# MotorsAndLighthouseShield.net
KiCad netlist of a schematic drawn in EAGLE
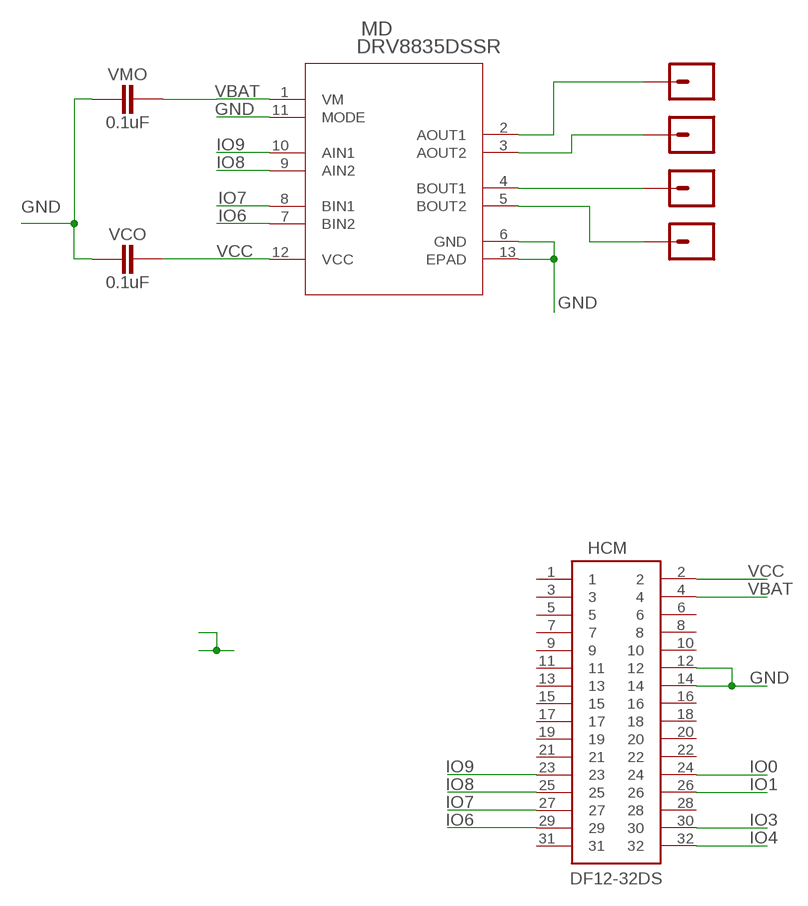
[diagram p0: schematic, sheet 1]
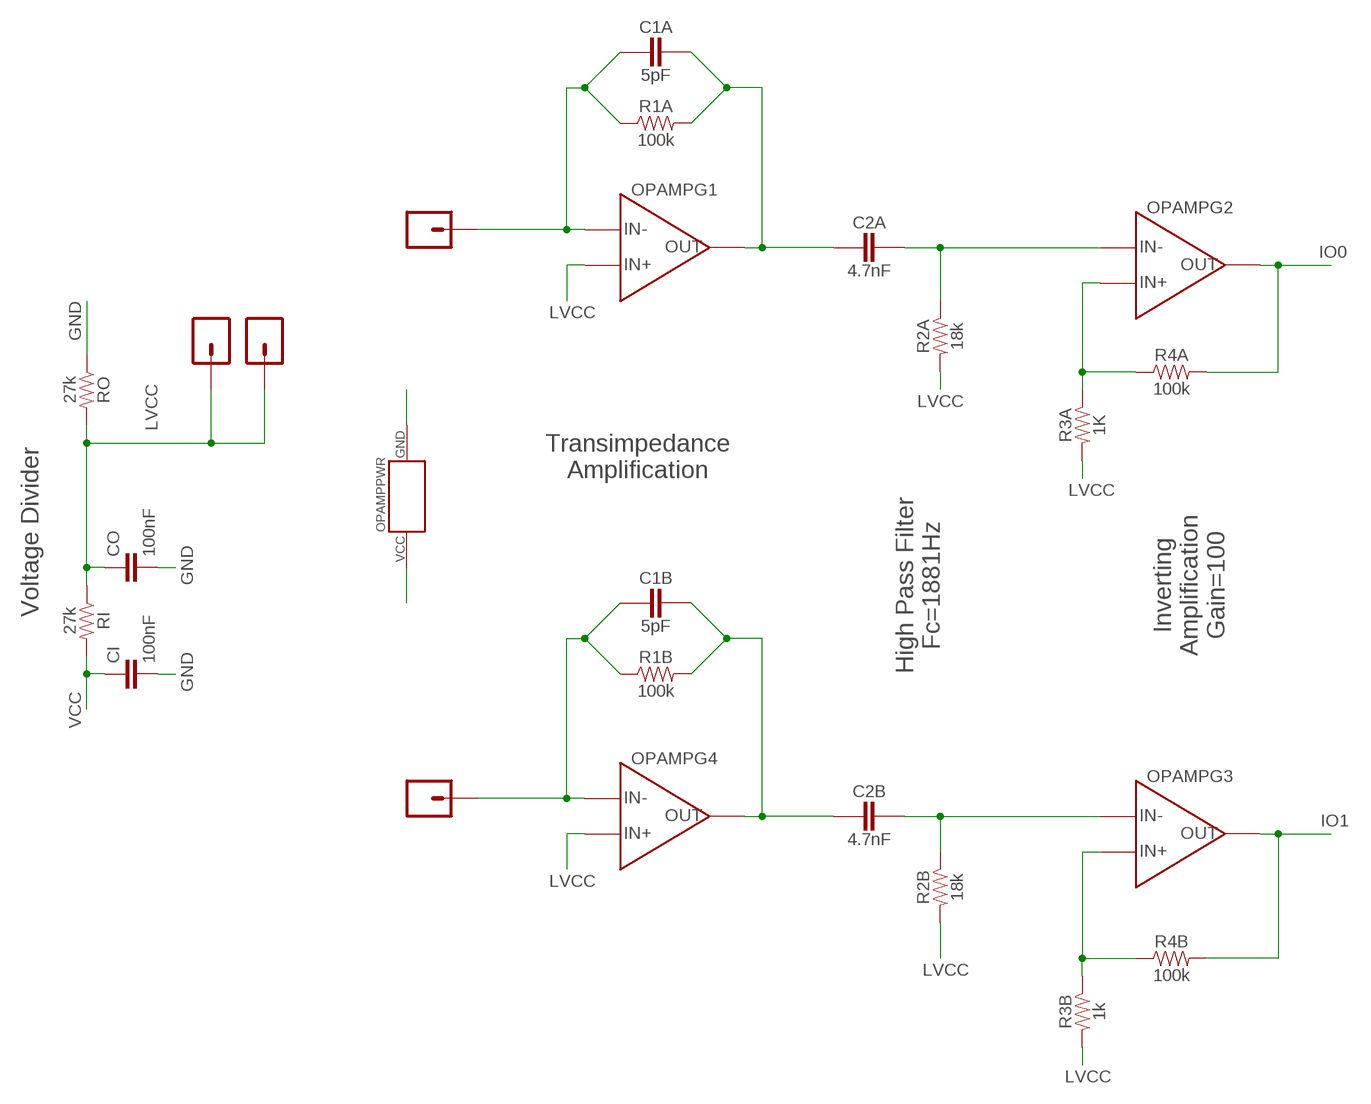
[diagram p1: schematic, sheet 2]

(export (version "E")
  (design (tool "Eeschema 10.0.6"))
  (components
    (comp (ref "AO1")
      (value "SINGLE-THROUGH-HOLE")
      (footprint "eagle-import:SINGLE-THROUGH-HOLE")
      (libsource (lib "eagle-import") (part "SINGLE-THROUGH-HOLE"))
    )
    (comp (ref "AO2")
      (value "SINGLE-THROUGH-HOLE")
      (footprint "eagle-import:SINGLE-THROUGH-HOLE")
      (libsource (lib "eagle-import") (part "SINGLE-THROUGH-HOLE"))
    )
    (comp (ref "B02")
      (value "SINGLE-THROUGH-HOLE")
      (footprint "eagle-import:SINGLE-THROUGH-HOLE")
      (libsource (lib "eagle-import") (part "SINGLE-THROUGH-HOLE"))
    )
    (comp (ref "BO1")
      (value "SINGLE-THROUGH-HOLE")
      (footprint "eagle-import:SINGLE-THROUGH-HOLE")
      (libsource (lib "eagle-import") (part "SINGLE-THROUGH-HOLE"))
    )
    (comp (ref "HCM")
      (value "HIROSE-DF12-32DSMALE")
      (footprint "eagle-import:DF12(3.0)-32DS-0.5V(86)-MALE")
      (libsource (lib "eagle-import") (part "HIROSE-DF12-32DSMALE"))
    )
    (comp (ref "MD")
      (value "DRV8835DSSR")
      (footprint "eagle-import:DSS12_P9X2")
      (libsource (lib "eagle-import") (part "DRV8835DSSR"))
    )
    (comp (ref "VCO")
      (value "0.1uF")
      (footprint "eagle-import:PASSIVE-0603")
      (libsource (lib "eagle-import") (part "CAPACITOR"))
    )
    (comp (ref "VMO")
      (value "0.1uF")
      (footprint "eagle-import:PASSIVE-0603")
      (libsource (lib "eagle-import") (part "CAPACITOR"))
    )
    (comp (ref "C1A")
      (value "5pF")
      (footprint "eagle-import:PASSIVE-0603")
      (libsource (lib "eagle-import") (part "CAPACITOR"))
    )
    (comp (ref "C1B")
      (value "5pF")
      (footprint "eagle-import:PASSIVE-0603")
      (libsource (lib "eagle-import") (part "CAPACITOR"))
    )
    (comp (ref "C2A")
      (value "4.7nF")
      (footprint "eagle-import:PASSIVE-0603")
      (libsource (lib "eagle-import") (part "CAPACITOR"))
    )
    (comp (ref "C2B")
      (value "4.7nF")
      (footprint "eagle-import:PASSIVE-0603")
      (libsource (lib "eagle-import") (part "CAPACITOR"))
    )
    (comp (ref "CI")
      (value "100nF")
      (footprint "eagle-import:0603")
      (libsource (lib "eagle-import") (part "4.7PF-0603-50V-5%"))
    )
    (comp (ref "CO")
      (value "100nF")
      (footprint "eagle-import:0603")
      (libsource (lib "eagle-import") (part "4.7PF-0603-50V-5%"))
    )
    (comp (ref "DIA")
      (value "SINGLE-THROUGH-HOLE")
      (footprint "eagle-import:SINGLE-THROUGH-HOLE")
      (libsource (lib "eagle-import") (part "SINGLE-THROUGH-HOLE"))
    )
    (comp (ref "DIB")
      (value "SINGLE-THROUGH-HOLE")
      (footprint "eagle-import:SINGLE-THROUGH-HOLE")
      (libsource (lib "eagle-import") (part "SINGLE-THROUGH-HOLE"))
    )
    (comp (ref "DOA")
      (value "SINGLE-THROUGH-HOLE")
      (footprint "eagle-import:SINGLE-THROUGH-HOLE")
      (libsource (lib "eagle-import") (part "SINGLE-THROUGH-HOLE"))
    )
    (comp (ref "DOB")
      (value "SINGLE-THROUGH-HOLE")
      (footprint "eagle-import:SINGLE-THROUGH-HOLE")
      (libsource (lib "eagle-import") (part "SINGLE-THROUGH-HOLE"))
    )
    (comp (ref "OPAMP")
      (value "TLV2464IPW")
      (footprint "eagle-import:PW14")
      (libsource (lib "eagle-import") (part "TLV2464IPW"))
    )
    (comp (ref "R1A")
      (value "100k")
      (footprint "eagle-import:PASSIVE-0603")
      (libsource (lib "eagle-import") (part "RESISTOR"))
    )
    (comp (ref "R1B")
      (value "100k")
      (footprint "eagle-import:PASSIVE-0603")
      (libsource (lib "eagle-import") (part "RESISTOR"))
    )
    (comp (ref "R2A")
      (value "18k")
      (footprint "eagle-import:PASSIVE-0603")
      (libsource (lib "eagle-import") (part "RESISTOR"))
    )
    (comp (ref "R2B")
      (value "18k")
      (footprint "eagle-import:PASSIVE-0603")
      (libsource (lib "eagle-import") (part "RESISTOR"))
    )
    (comp (ref "R3A")
      (value "1K")
      (footprint "eagle-import:PASSIVE-0603")
      (libsource (lib "eagle-import") (part "RESISTOR"))
    )
    (comp (ref "R3B")
      (value "1k")
      (footprint "eagle-import:PASSIVE-0603")
      (libsource (lib "eagle-import") (part "RESISTOR"))
    )
    (comp (ref "R4A")
      (value "100k")
      (footprint "eagle-import:PASSIVE-0603")
      (libsource (lib "eagle-import") (part "RESISTOR"))
    )
    (comp (ref "R4B")
      (value "100k")
      (footprint "eagle-import:PASSIVE-0603")
      (libsource (lib "eagle-import") (part "RESISTOR"))
    )
    (comp (ref "RI")
      (value "27k")
      (footprint "eagle-import:0603")
      (libsource (lib "eagle-import") (part "100KOHM-0603-1/10W-1%"))
    )
    (comp (ref "RO")
      (value "27k")
      (footprint "eagle-import:0603")
      (libsource (lib "eagle-import") (part "100KOHM-0603-1/10W-1%"))
    )
  )
  (nets
    (net (code "1") (name "GND") (class "Default")
      (node (ref "CI") (pin "2") (pinfunction "2_2") (pintype "passive"))
      (node (ref "CO") (pin "2") (pinfunction "2_2") (pintype "passive"))
      (node (ref "HCM") (pin "12") (pinfunction "12_12") (pintype "bidirectional"))
      (node (ref "HCM") (pin "14") (pinfunction "14_14") (pintype "bidirectional"))
      (node (ref "MD") (pin "11") (pinfunction "MODE_11") (pintype "input"))
      (node (ref "MD") (pin "13") (pinfunction "EPAD_13") (pintype "passive"))
      (node (ref "MD") (pin "6") (pinfunction "GND_6") (pintype "power_in"))
      (node (ref "OPAMP") (pin "11") (pinfunction "GND_11") (pintype "bidirectional"))
      (node (ref "RO") (pin "1") (pinfunction "1_1") (pintype "passive"))
      (node (ref "VCO") (pin "1") (pinfunction "1_1") (pintype "passive"))
      (node (ref "VMO") (pin "1") (pinfunction "1_1") (pintype "passive"))
    )
    (net (code "2") (name "IO0") (class "Default")
      (node (ref "HCM") (pin "24") (pinfunction "24_24") (pintype "bidirectional"))
      (node (ref "OPAMP") (pin "7") (pinfunction "OUT_7") (pintype "bidirectional"))
      (node (ref "R4A") (pin "2") (pinfunction "2_2") (pintype "passive"))
    )
    (net (code "3") (name "IO1") (class "Default")
      (node (ref "HCM") (pin "26") (pinfunction "26_26") (pintype "bidirectional"))
      (node (ref "OPAMP") (pin "8") (pinfunction "OUT_8") (pintype "bidirectional"))
      (node (ref "R4B") (pin "2") (pinfunction "2_2") (pintype "passive"))
    )
    (net (code "4") (name "IO3") (class "Default")
      (node (ref "HCM") (pin "30") (pinfunction "30_30") (pintype "bidirectional"))
    )
    (net (code "5") (name "IO4") (class "Default")
      (node (ref "HCM") (pin "32") (pinfunction "32_32") (pintype "bidirectional"))
    )
    (net (code "6") (name "IO6") (class "Default")
      (node (ref "HCM") (pin "29") (pinfunction "29_29") (pintype "bidirectional"))
      (node (ref "MD") (pin "7") (pinfunction "BIN2_7") (pintype "input"))
    )
    (net (code "7") (name "IO7") (class "Default")
      (node (ref "HCM") (pin "27") (pinfunction "27_27") (pintype "bidirectional"))
      (node (ref "MD") (pin "8") (pinfunction "BIN1_8") (pintype "input"))
    )
    (net (code "8") (name "IO8") (class "Default")
      (node (ref "HCM") (pin "25") (pinfunction "25_25") (pintype "bidirectional"))
      (node (ref "MD") (pin "9") (pinfunction "AIN2_9") (pintype "input"))
    )
    (net (code "9") (name "IO9") (class "Default")
      (node (ref "HCM") (pin "23") (pinfunction "23_23") (pintype "bidirectional"))
      (node (ref "MD") (pin "10") (pinfunction "AIN1_10") (pintype "input"))
    )
    (net (code "10") (name "LVCC") (class "Default")
      (node (ref "CO") (pin "1") (pinfunction "1_1") (pintype "passive"))
      (node (ref "DOA") (pin "1") (pinfunction "1_1") (pintype "passive"))
      (node (ref "DOB") (pin "1") (pinfunction "1_1") (pintype "passive"))
      (node (ref "OPAMP") (pin "12") (pinfunction "IN+_12") (pintype "bidirectional"))
      (node (ref "OPAMP") (pin "3") (pinfunction "IN+_3") (pintype "bidirectional"))
      (node (ref "R2A") (pin "2") (pinfunction "2_2") (pintype "passive"))
      (node (ref "R2B") (pin "2") (pinfunction "2_2") (pintype "passive"))
      (node (ref "R3A") (pin "2") (pinfunction "2_2") (pintype "passive"))
      (node (ref "R3B") (pin "2") (pinfunction "2_2") (pintype "passive"))
      (node (ref "RI") (pin "1") (pinfunction "1_1") (pintype "passive"))
      (node (ref "RO") (pin "2") (pinfunction "2_2") (pintype "passive"))
    )
    (net (code "11") (name "Net-(MD-AOUT1)") (class "Default")
      (node (ref "BO1") (pin "1") (pinfunction "1_1") (pintype "passive"))
      (node (ref "MD") (pin "2") (pinfunction "AOUT1_2") (pintype "output"))
    )
    (net (code "12") (name "Net-(MD-AOUT2)") (class "Default")
      (node (ref "B02") (pin "1") (pinfunction "1_1") (pintype "passive"))
      (node (ref "MD") (pin "3") (pinfunction "AOUT2_3") (pintype "output"))
    )
    (net (code "13") (name "Net-(MD-BOUT1)") (class "Default")
      (node (ref "AO1") (pin "1") (pinfunction "1_1") (pintype "passive"))
      (node (ref "MD") (pin "4") (pinfunction "BOUT1_4") (pintype "output"))
    )
    (net (code "14") (name "Net-(MD-BOUT2)") (class "Default")
      (node (ref "AO2") (pin "1") (pinfunction "1_1") (pintype "passive"))
      (node (ref "MD") (pin "5") (pinfunction "BOUT2_5") (pintype "output"))
    )
    (net (code "15") (name "Net-(OPAMPA-IN-)") (class "Default")
      (node (ref "C1A") (pin "1") (pinfunction "1_1") (pintype "passive"))
      (node (ref "DIA") (pin "1") (pinfunction "1_1") (pintype "passive"))
      (node (ref "OPAMP") (pin "2") (pinfunction "IN-_2") (pintype "bidirectional"))
      (node (ref "R1A") (pin "1") (pinfunction "1_1") (pintype "passive"))
    )
    (net (code "16") (name "Net-(OPAMPA-OUT)") (class "Default")
      (node (ref "C1A") (pin "2") (pinfunction "2_2") (pintype "passive"))
      (node (ref "C2A") (pin "1") (pinfunction "1_1") (pintype "passive"))
      (node (ref "OPAMP") (pin "1") (pinfunction "OUT_1") (pintype "bidirectional"))
      (node (ref "R1A") (pin "2") (pinfunction "2_2") (pintype "passive"))
    )
    (net (code "17") (name "Net-(OPAMPB-IN+)") (class "Default")
      (node (ref "OPAMP") (pin "5") (pinfunction "IN+_5") (pintype "bidirectional"))
      (node (ref "R3A") (pin "1") (pinfunction "1_1") (pintype "passive"))
      (node (ref "R4A") (pin "1") (pinfunction "1_1") (pintype "passive"))
    )
    (net (code "18") (name "Net-(OPAMPB-IN-)") (class "Default")
      (node (ref "C2A") (pin "2") (pinfunction "2_2") (pintype "passive"))
      (node (ref "OPAMP") (pin "6") (pinfunction "IN-_6") (pintype "bidirectional"))
      (node (ref "R2A") (pin "1") (pinfunction "1_1") (pintype "passive"))
    )
    (net (code "19") (name "Net-(OPAMPC-IN+)") (class "Default")
      (node (ref "OPAMP") (pin "10") (pinfunction "IN+_10") (pintype "bidirectional"))
      (node (ref "R3B") (pin "1") (pinfunction "1_1") (pintype "passive"))
      (node (ref "R4B") (pin "1") (pinfunction "1_1") (pintype "passive"))
    )
    (net (code "20") (name "Net-(OPAMPC-IN-)") (class "Default")
      (node (ref "C2B") (pin "2") (pinfunction "2_2") (pintype "passive"))
      (node (ref "OPAMP") (pin "9") (pinfunction "IN-_9") (pintype "bidirectional"))
      (node (ref "R2B") (pin "1") (pinfunction "1_1") (pintype "passive"))
    )
    (net (code "21") (name "Net-(OPAMPD-IN-)") (class "Default")
      (node (ref "C1B") (pin "1") (pinfunction "1_1") (pintype "passive"))
      (node (ref "DIB") (pin "1") (pinfunction "1_1") (pintype "passive"))
      (node (ref "OPAMP") (pin "13") (pinfunction "IN-_13") (pintype "bidirectional"))
      (node (ref "R1B") (pin "1") (pinfunction "1_1") (pintype "passive"))
    )
    (net (code "22") (name "Net-(OPAMPD-OUT)") (class "Default")
      (node (ref "C1B") (pin "2") (pinfunction "2_2") (pintype "passive"))
      (node (ref "C2B") (pin "1") (pinfunction "1_1") (pintype "passive"))
      (node (ref "OPAMP") (pin "14") (pinfunction "OUT_14") (pintype "bidirectional"))
      (node (ref "R1B") (pin "2") (pinfunction "2_2") (pintype "passive"))
    )
    (net (code "23") (name "VBAT") (class "Default")
      (node (ref "HCM") (pin "4") (pinfunction "4_4") (pintype "bidirectional"))
      (node (ref "MD") (pin "1") (pinfunction "VM_1") (pintype "power_in"))
      (node (ref "VMO") (pin "2") (pinfunction "2_2") (pintype "passive"))
    )
    (net (code "24") (name "VCC") (class "Default")
      (node (ref "CI") (pin "1") (pinfunction "1_1") (pintype "passive"))
      (node (ref "HCM") (pin "2") (pinfunction "2_2") (pintype "bidirectional"))
      (node (ref "MD") (pin "12") (pinfunction "VCC_12") (pintype "power_in"))
      (node (ref "OPAMP") (pin "4") (pinfunction "VCC_4") (pintype "bidirectional"))
      (node (ref "RI") (pin "2") (pinfunction "2_2") (pintype "passive"))
      (node (ref "VCO") (pin "2") (pinfunction "2_2") (pintype "passive"))
    )
    (net (code "25") (name "unconnected-(HCM-Pad1)") (class "Default")
      (node (ref "HCM") (pin "1") (pinfunction "1_1") (pintype "bidirectional"))
    )
    (net (code "26") (name "unconnected-(HCM-Pad3)") (class "Default")
      (node (ref "HCM") (pin "3") (pinfunction "3_3") (pintype "bidirectional"))
    )
    (net (code "27") (name "unconnected-(HCM-Pad5)") (class "Default")
      (node (ref "HCM") (pin "5") (pinfunction "5_5") (pintype "bidirectional"))
    )
    (net (code "28") (name "unconnected-(HCM-Pad6)") (class "Default")
      (node (ref "HCM") (pin "6") (pinfunction "6_6") (pintype "bidirectional"))
    )
    (net (code "29") (name "unconnected-(HCM-Pad7)") (class "Default")
      (node (ref "HCM") (pin "7") (pinfunction "7_7") (pintype "bidirectional"))
    )
    (net (code "30") (name "unconnected-(HCM-Pad8)") (class "Default")
      (node (ref "HCM") (pin "8") (pinfunction "8_8") (pintype "bidirectional"))
    )
    (net (code "31") (name "unconnected-(HCM-Pad9)") (class "Default")
      (node (ref "HCM") (pin "9") (pinfunction "9_9") (pintype "bidirectional"))
    )
    (net (code "32") (name "unconnected-(HCM-Pad10)") (class "Default")
      (node (ref "HCM") (pin "10") (pinfunction "10_10") (pintype "bidirectional"))
    )
    (net (code "33") (name "unconnected-(HCM-Pad11)") (class "Default")
      (node (ref "HCM") (pin "11") (pinfunction "11_11") (pintype "bidirectional"))
    )
    (net (code "34") (name "unconnected-(HCM-Pad13)") (class "Default")
      (node (ref "HCM") (pin "13") (pinfunction "13_13") (pintype "bidirectional"))
    )
    (net (code "35") (name "unconnected-(HCM-Pad15)") (class "Default")
      (node (ref "HCM") (pin "15") (pinfunction "15_15") (pintype "bidirectional"))
    )
    (net (code "36") (name "unconnected-(HCM-Pad16)") (class "Default")
      (node (ref "HCM") (pin "16") (pinfunction "16_16") (pintype "bidirectional"))
    )
    (net (code "37") (name "unconnected-(HCM-Pad17)") (class "Default")
      (node (ref "HCM") (pin "17") (pinfunction "17_17") (pintype "bidirectional"))
    )
    (net (code "38") (name "unconnected-(HCM-Pad18)") (class "Default")
      (node (ref "HCM") (pin "18") (pinfunction "18_18") (pintype "bidirectional"))
    )
    (net (code "39") (name "unconnected-(HCM-Pad19)") (class "Default")
      (node (ref "HCM") (pin "19") (pinfunction "19_19") (pintype "bidirectional"))
    )
    (net (code "40") (name "unconnected-(HCM-Pad20)") (class "Default")
      (node (ref "HCM") (pin "20") (pinfunction "20_20") (pintype "bidirectional"))
    )
    (net (code "41") (name "unconnected-(HCM-Pad21)") (class "Default")
      (node (ref "HCM") (pin "21") (pinfunction "21_21") (pintype "bidirectional"))
    )
    (net (code "42") (name "unconnected-(HCM-Pad22)") (class "Default")
      (node (ref "HCM") (pin "22") (pinfunction "22_22") (pintype "bidirectional"))
    )
    (net (code "43") (name "unconnected-(HCM-Pad28)") (class "Default")
      (node (ref "HCM") (pin "28") (pinfunction "28_28") (pintype "bidirectional"))
    )
    (net (code "44") (name "unconnected-(HCM-Pad31)") (class "Default")
      (node (ref "HCM") (pin "31") (pinfunction "31_31") (pintype "bidirectional"))
    )
  )
)
